# power_electronicsV5_1.net
KiCad netlist of a schematic drawn in EAGLE
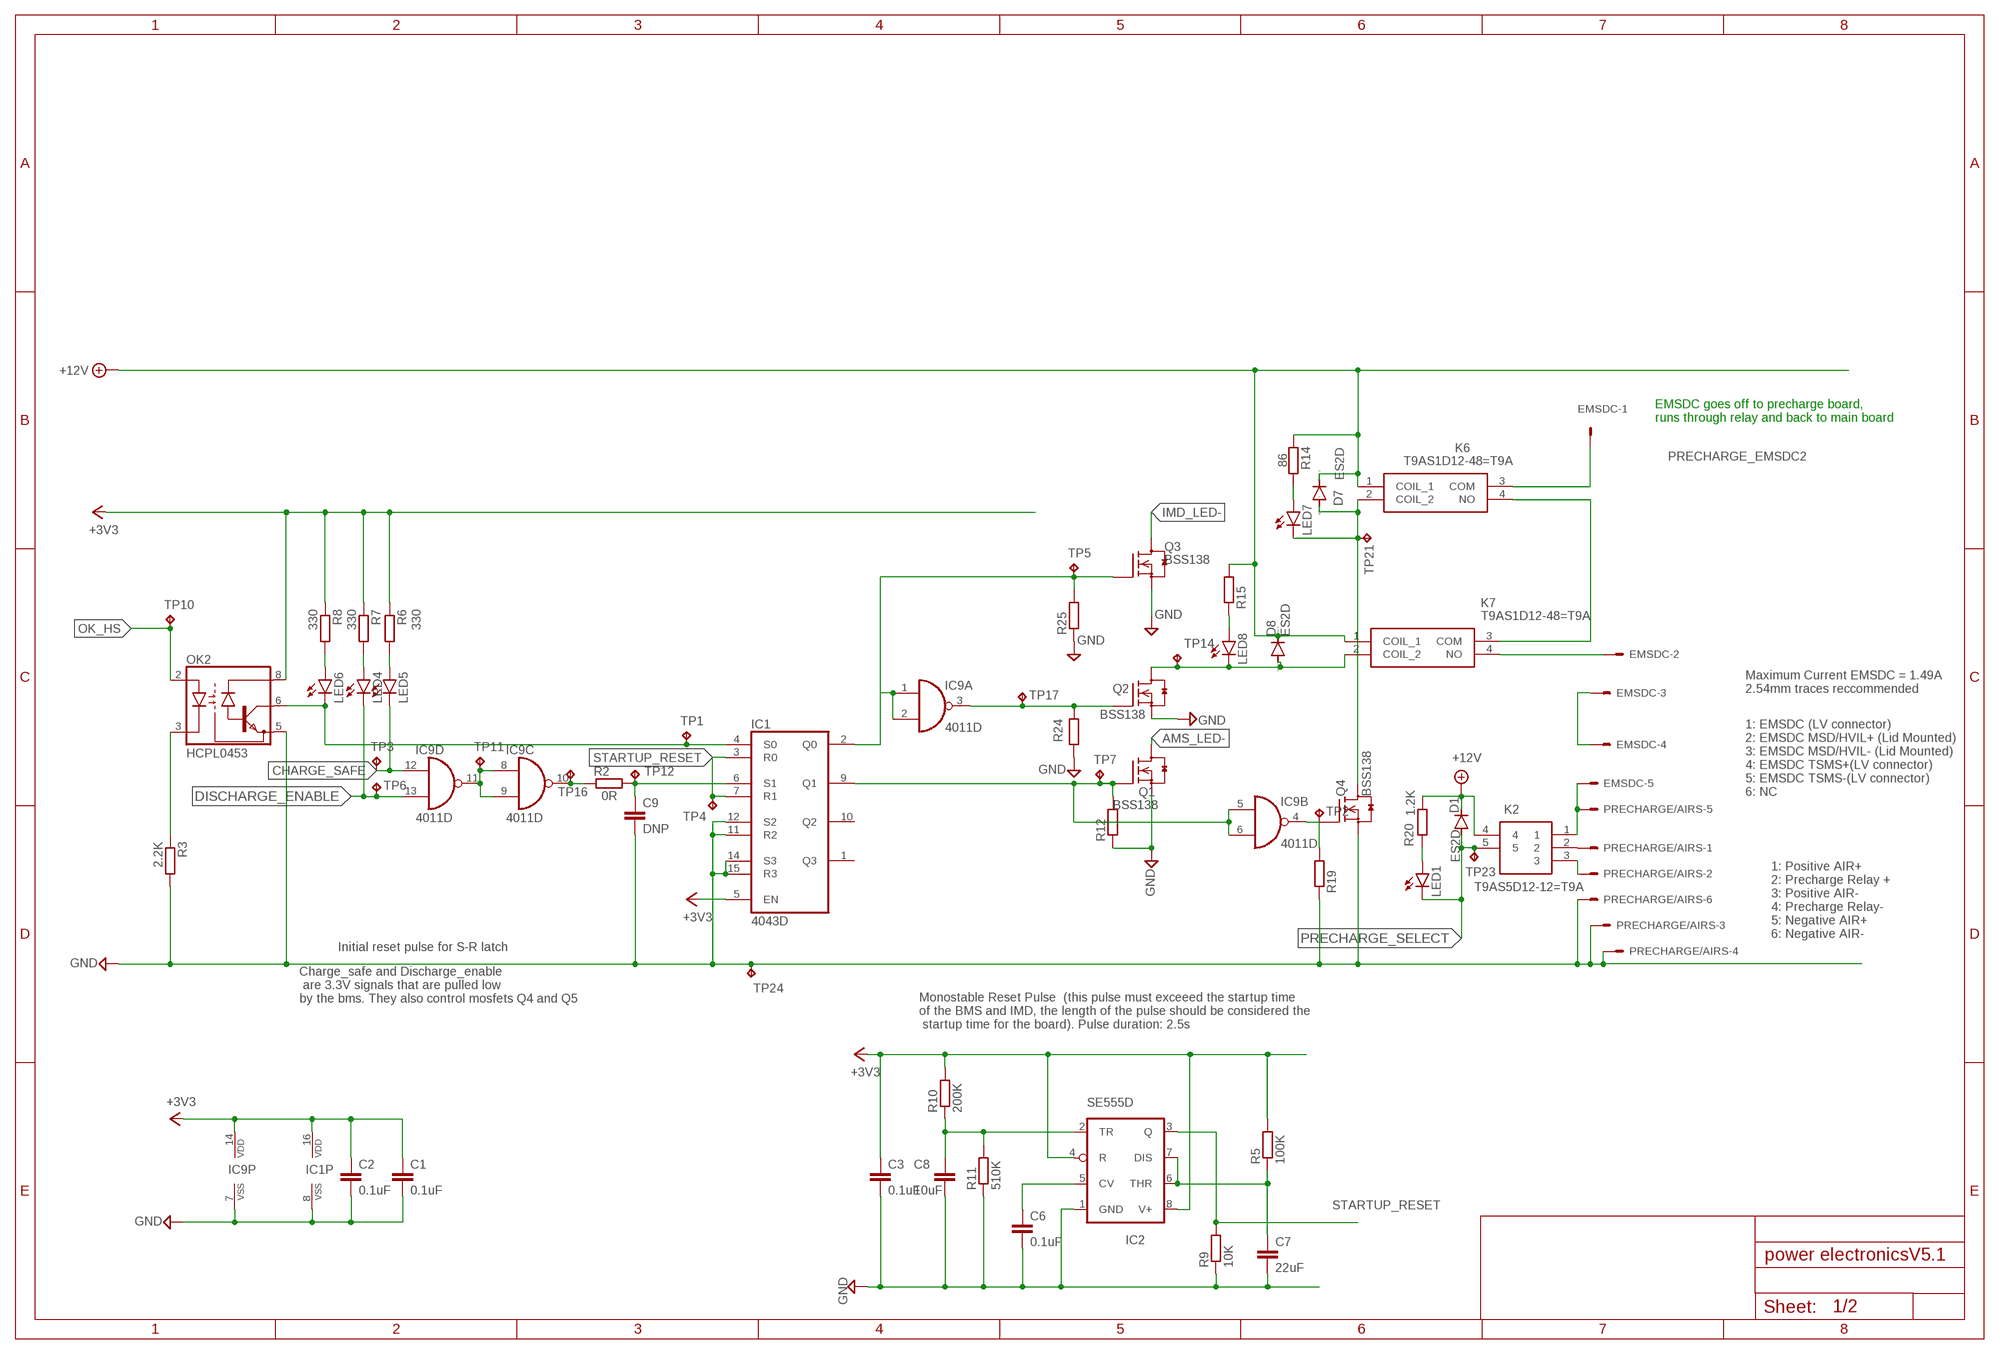
[diagram p0: schematic, sheet 1]
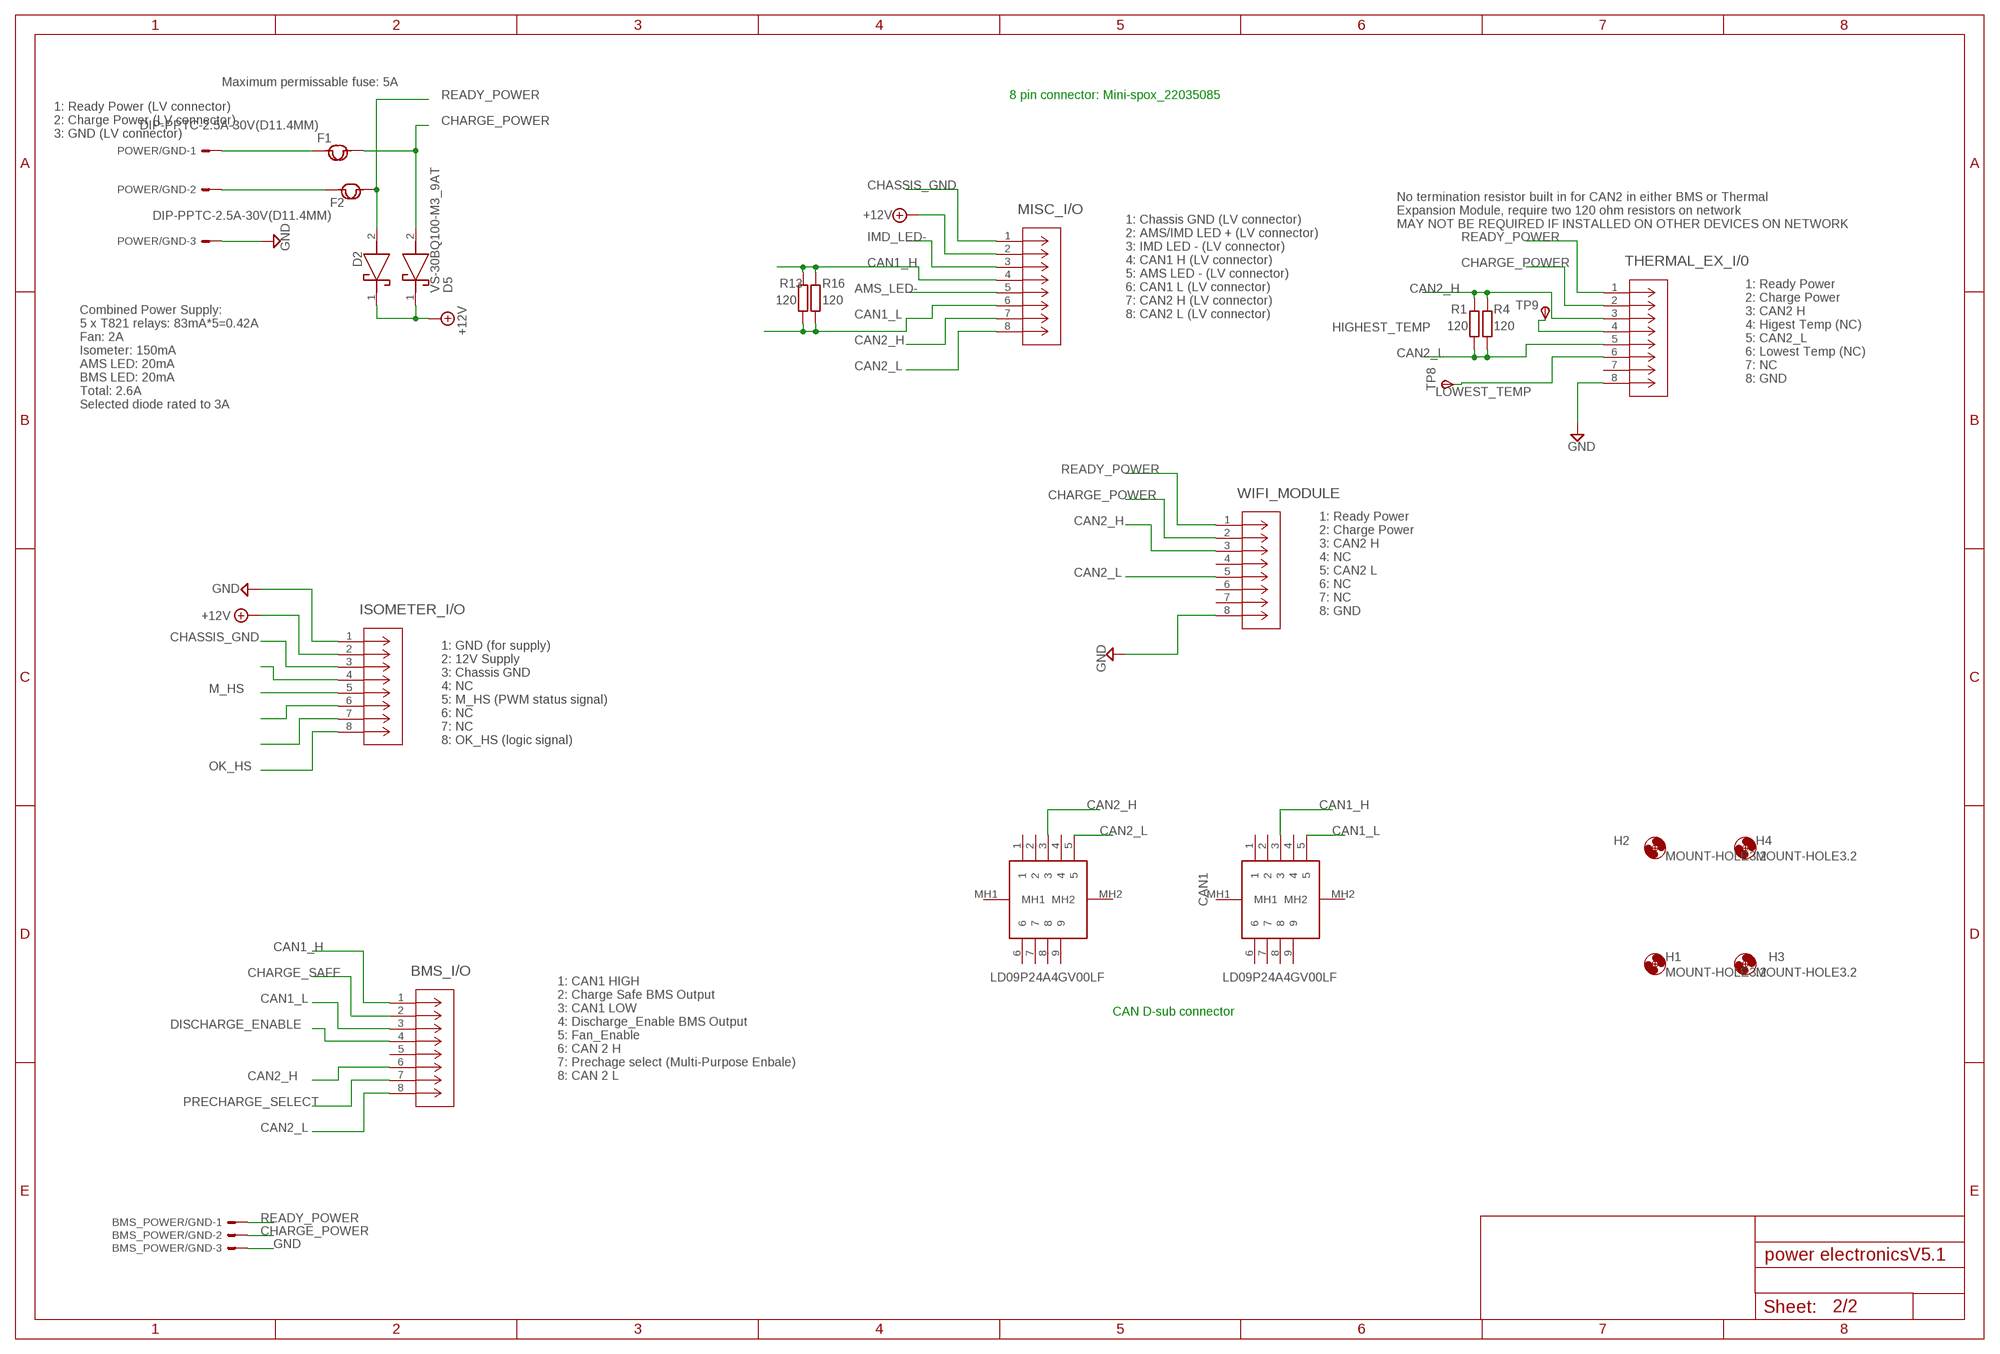
[diagram p1: schematic, sheet 2]

(export (version "E")
  (design (tool "Eeschema 10.0.6"))
  (components
    (comp (ref "C1")
      (value "0.1uF")
      (footprint "eagle-import:C0805")
      (fields (field (name "POPULARITY") "88F"))
      (libsource (lib "eagle-import") (part "C-EUC0805"))
    )
    (comp (ref "C2")
      (value "0.1uF")
      (footprint "eagle-import:C0805")
      (libsource (lib "eagle-import") (part "C-EUC0805"))
    )
    (comp (ref "C3")
      (value "0.1uF")
      (footprint "eagle-import:C0805")
      (libsource (lib "eagle-import") (part "C-EUC0805"))
    )
    (comp (ref "C6")
      (value "0.1uF")
      (footprint "eagle-import:C0805")
      (libsource (lib "eagle-import") (part "C-EUC0805"))
    )
    (comp (ref "C7")
      (value "22uF")
      (footprint "eagle-import:C1206")
      (libsource (lib "eagle-import") (part "C-EUC1206"))
    )
    (comp (ref "C8")
      (value "10uF")
      (footprint "eagle-import:C0805")
      (libsource (lib "eagle-import") (part "C-EUC0805"))
    )
    (comp (ref "C9")
      (value "DNP")
      (footprint "eagle-import:C0805K")
      (libsource (lib "eagle-import") (part "C-EUC0805K"))
    )
    (comp (ref "D1")
      (value "ES2D")
      (footprint "eagle-import:SMB")
      (libsource (lib "eagle-import") (part "ES2D"))
    )
    (comp (ref "D7")
      (value "ES2D")
      (footprint "eagle-import:SMB")
      (libsource (lib "eagle-import") (part "ES2D"))
    )
    (comp (ref "D8")
      (value "ES2D")
      (footprint "eagle-import:SMB")
      (libsource (lib "eagle-import") (part "ES2D"))
    )
    (comp (ref "EMSDC")
      (value "KK-156-6")
      (footprint "eagle-import:KK-156-6")
      (fields (field (name "MF") "MOLEX"))
      (libsource (lib "eagle-import") (part "KK-156-6"))
    )
    (comp (ref "IC1")
      (value "4043D")
      (footprint "eagle-import:SO16")
      (libsource (lib "eagle-import") (part "4043D"))
    )
    (comp (ref "IC2")
      (value "SE555D")
      (footprint "eagle-import:SO08")
      (libsource (lib "eagle-import") (part "555DSE"))
    )
    (comp (ref "IC9")
      (value "4011D")
      (footprint "eagle-import:SO14")
      (libsource (lib "eagle-import") (part "4011D"))
    )
    (comp (ref "K2")
      (value "T9AS5D12-12=T9A")
      (footprint "eagle-import:T9AS1D12")
      (fields (field (name "RS_PART_NUMBER") "6802528"))
      (libsource (lib "eagle-import") (part "T9AS5D12-12=T9A"))
    )
    (comp (ref "K6")
      (value "T9AS1D12-48=T9A")
      (footprint "eagle-import:T9AS1D1248T9A")
      (libsource (lib "eagle-import") (part "T9AS1D12-48=T9A"))
    )
    (comp (ref "K7")
      (value "T9AS1D12-48=T9A")
      (footprint "eagle-import:T9AS1D1248T9A")
      (libsource (lib "eagle-import") (part "T9AS1D12-48=T9A"))
    )
    (comp (ref "LED1")
      (value "LEDSML0805")
      (footprint "eagle-import:SML0805")
      (libsource (lib "eagle-import") (part "LEDSML0805"))
    )
    (comp (ref "LED4")
      (value "LEDSML0805")
      (footprint "eagle-import:SML0805")
      (libsource (lib "eagle-import") (part "LEDSML0805"))
    )
    (comp (ref "LED5")
      (value "LEDSML0805")
      (footprint "eagle-import:SML0805")
      (libsource (lib "eagle-import") (part "LEDSML0805"))
    )
    (comp (ref "LED6")
      (value "LEDSML0805")
      (footprint "eagle-import:SML0805")
      (libsource (lib "eagle-import") (part "LEDSML0805"))
    )
    (comp (ref "LED7")
      (value "LEDSML0805")
      (footprint "eagle-import:SML0805")
      (libsource (lib "eagle-import") (part "LEDSML0805"))
    )
    (comp (ref "LED8")
      (value "LEDSML0805")
      (footprint "eagle-import:SML0805")
      (libsource (lib "eagle-import") (part "LEDSML0805"))
    )
    (comp (ref "OK2")
      (value "HCPL0453")
      (footprint "eagle-import:SOIC08")
      (fields (field (name "MF") "AGILENT TECHNOLOGIES") (field (name "MPN") "HCPL-0453-000E"))
      (libsource (lib "eagle-import") (part "HCPL0453"))
    )
    (comp (ref "PRECHARGE/AIRS")
      (value "KK-156-6")
      (footprint "eagle-import:KK-156-6")
      (fields (field (name "MF") "MOLEX"))
      (libsource (lib "eagle-import") (part "KK-156-6"))
    )
    (comp (ref "Q1")
      (value "BSS138")
      (footprint "eagle-import:SOT23")
      (libsource (lib "eagle-import") (part "BSS138"))
    )
    (comp (ref "Q2")
      (value "BSS138")
      (footprint "eagle-import:SOT23")
      (libsource (lib "eagle-import") (part "BSS138"))
    )
    (comp (ref "Q3")
      (value "BSS138")
      (footprint "eagle-import:SOT23")
      (libsource (lib "eagle-import") (part "BSS138"))
    )
    (comp (ref "Q4")
      (value "BSS138")
      (footprint "eagle-import:SOT23")
      (libsource (lib "eagle-import") (part "BSS138"))
    )
    (comp (ref "R2")
      (value "0R")
      (footprint "eagle-import:R0805")
      (libsource (lib "eagle-import") (part "R-EU_R0805"))
    )
    (comp (ref "R3")
      (value "2.2K")
      (footprint "eagle-import:R0805")
      (libsource (lib "eagle-import") (part "R-EU_R0805"))
    )
    (comp (ref "R5")
      (value "100K")
      (footprint "eagle-import:R0805")
      (libsource (lib "eagle-import") (part "R-EU_R0805"))
    )
    (comp (ref "R6")
      (value "330")
      (footprint "eagle-import:R0805")
      (libsource (lib "eagle-import") (part "R-EU_R0805"))
    )
    (comp (ref "R7")
      (value "330")
      (footprint "eagle-import:R0805")
      (libsource (lib "eagle-import") (part "R-EU_R0805"))
    )
    (comp (ref "R8")
      (value "330")
      (footprint "eagle-import:R0805")
      (libsource (lib "eagle-import") (part "R-EU_R0805"))
    )
    (comp (ref "R9")
      (value "10K")
      (footprint "eagle-import:R0805")
      (libsource (lib "eagle-import") (part "R-EU_R0805"))
    )
    (comp (ref "R10")
      (value "200K")
      (footprint "eagle-import:R0805")
      (libsource (lib "eagle-import") (part "R-EU_R0805"))
    )
    (comp (ref "R11")
      (value "510K")
      (footprint "eagle-import:R0805")
      (libsource (lib "eagle-import") (part "R-EU_R0805"))
    )
    (comp (ref "R12")
      (value "R-EU_R0805")
      (footprint "eagle-import:R0805")
      (libsource (lib "eagle-import") (part "R-EU_R0805"))
    )
    (comp (ref "R14")
      (value "R-EU_R0805")
      (footprint "eagle-import:R0805")
      (fields (field (name "POPULARITY") "86"))
      (libsource (lib "eagle-import") (part "R-EU_R0805"))
    )
    (comp (ref "R15")
      (value "R-EU_R0805")
      (footprint "eagle-import:R0805")
      (libsource (lib "eagle-import") (part "R-EU_R0805"))
    )
    (comp (ref "R19")
      (value "R-EU_R0805")
      (footprint "eagle-import:R0805")
      (libsource (lib "eagle-import") (part "R-EU_R0805"))
    )
    (comp (ref "R20")
      (value "1.2K")
      (footprint "eagle-import:R0805")
      (libsource (lib "eagle-import") (part "R-EU_R0805"))
    )
    (comp (ref "R24")
      (value "R-EU_R0805")
      (footprint "eagle-import:R0805")
      (libsource (lib "eagle-import") (part "R-EU_R0805"))
    )
    (comp (ref "R25")
      (value "R-EU_R0805")
      (footprint "eagle-import:R0805")
      (libsource (lib "eagle-import") (part "R-EU_R0805"))
    )
    (comp (ref "TP1")
      (value "TPPAD1-17")
      (footprint "eagle-import:P1-17")
      (libsource (lib "eagle-import") (part "TPPAD1-17"))
    )
    (comp (ref "TP2")
      (value "TPPAD1-17")
      (footprint "eagle-import:P1-17")
      (libsource (lib "eagle-import") (part "TPPAD1-17"))
    )
    (comp (ref "TP3")
      (value "TPPAD1-17")
      (footprint "eagle-import:P1-17")
      (libsource (lib "eagle-import") (part "TPPAD1-17"))
    )
    (comp (ref "TP4")
      (value "TPPAD1-17")
      (footprint "eagle-import:P1-17")
      (libsource (lib "eagle-import") (part "TPPAD1-17"))
    )
    (comp (ref "TP5")
      (value "TPPAD1-17")
      (footprint "eagle-import:P1-17")
      (libsource (lib "eagle-import") (part "TPPAD1-17"))
    )
    (comp (ref "TP6")
      (value "TPPAD1-17")
      (footprint "eagle-import:P1-17")
      (libsource (lib "eagle-import") (part "TPPAD1-17"))
    )
    (comp (ref "TP7")
      (value "TPPAD1-17")
      (footprint "eagle-import:P1-17")
      (libsource (lib "eagle-import") (part "TPPAD1-17"))
    )
    (comp (ref "TP10")
      (value "TPPAD1-17")
      (footprint "eagle-import:P1-17")
      (libsource (lib "eagle-import") (part "TPPAD1-17"))
    )
    (comp (ref "TP11")
      (value "TPPAD1-17")
      (footprint "eagle-import:P1-17")
      (libsource (lib "eagle-import") (part "TPPAD1-17"))
    )
    (comp (ref "TP12")
      (value "TPPAD1-17")
      (footprint "eagle-import:P1-17")
      (libsource (lib "eagle-import") (part "TPPAD1-17"))
    )
    (comp (ref "TP14")
      (value "TPPAD1-17")
      (footprint "eagle-import:P1-17")
      (libsource (lib "eagle-import") (part "TPPAD1-17"))
    )
    (comp (ref "TP16")
      (value "TPPAD1-17")
      (footprint "eagle-import:P1-17")
      (libsource (lib "eagle-import") (part "TPPAD1-17"))
    )
    (comp (ref "TP17")
      (value "TPPAD1-17")
      (footprint "eagle-import:P1-17")
      (libsource (lib "eagle-import") (part "TPPAD1-17"))
    )
    (comp (ref "TP21")
      (value "TPPAD1-17")
      (footprint "eagle-import:P1-17")
      (libsource (lib "eagle-import") (part "TPPAD1-17"))
    )
    (comp (ref "TP23")
      (value "TPPAD1-17")
      (footprint "eagle-import:P1-17")
      (libsource (lib "eagle-import") (part "TPPAD1-17"))
    )
    (comp (ref "TP24")
      (value "TPPAD1-17")
      (footprint "eagle-import:P1-17")
      (libsource (lib "eagle-import") (part "TPPAD1-17"))
    )
    (comp (ref "BMS_I/O")
      (value "MINI-SPOX_22035085")
      (footprint "eagle-import:CON_22035085_MOL")
      (fields
        (field (name "MANUFACTURER_PART_NUMBER") "22035085")
        (field (name "COPYRIGHT") "Copyright (C) 2023 Ultra Librarian. All rights reserved.")
      )
      (libsource (lib "eagle-import") (part "MINI-SPOX_22035085"))
    )
    (comp (ref "BMS_POWER/GND")
      (value "KK-156-3")
      (footprint "eagle-import:KK-156-3")
      (fields (field (name "MF") "MOLEX"))
      (libsource (lib "eagle-import") (part "KK-156-3"))
    )
    (comp (ref "CAN1")
      (value "LD09P24A4GV00LF")
      (footprint "eagle-import:LD09P24A4GV00LF")
      (fields (field (name "MOUSER_PART_NUMBER") "649-LD09P24A4GV00LF"))
      (libsource (lib "eagle-import") (part "LD09P24A4GV00LF"))
    )
    (comp (ref "CAN2")
      (value "LD09P24A4GV00LF")
      (footprint "eagle-import:LD09P24A4GV00LF")
      (fields (field (name "MOUSER_PART_NUMBER") "649-LD09P24A4GV00LF"))
      (libsource (lib "eagle-import") (part "LD09P24A4GV00LF"))
    )
    (comp (ref "D2")
      (value "VS-30BQ100-M3_9AT")
      (footprint "eagle-import:DIOM7959X262N")
      (fields
        (field (name "MANUFACTURER_PART_NUMBER") "VS-30BQ100-M3/9AT")
        (field (name "MOUSER_PART_NUMBER") "78-VS-30BQ100-M39AT")
      )
      (libsource (lib "eagle-import") (part "VS-30BQ100-M3_9AT"))
    )
    (comp (ref "D5")
      (value "VS-30BQ100-M3_9AT")
      (footprint "eagle-import:DIOM7959X262N")
      (fields
        (field (name "MANUFACTURER_PART_NUMBER") "VS-30BQ100-M3/9AT")
        (field (name "MOUSER_PART_NUMBER") "78-VS-30BQ100-M39AT")
      )
      (libsource (lib "eagle-import") (part "VS-30BQ100-M3_9AT"))
    )
    (comp (ref "F1")
      (value "DIP-PPTC-2.5A-30V(D11.4MM)")
      (footprint "eagle-import:F2-5.1-11.4X3.0X18.3MM")
      (fields (field (name "MF") "Littelfuse") (field (name "MP") "30R250"))
      (libsource (lib "eagle-import") (part "DIP-PPTC-2.5A-30V(D11.4MM)"))
    )
    (comp (ref "F2")
      (value "DIP-PPTC-2.5A-30V(D11.4MM)")
      (footprint "eagle-import:F2-5.1-11.4X3.0X18.3MM")
      (fields (field (name "MF") "Littelfuse") (field (name "MP") "30R250"))
      (libsource (lib "eagle-import") (part "DIP-PPTC-2.5A-30V(D11.4MM)"))
    )
    (comp (ref "H1")
      (value "MOUNT-HOLE3.2")
      (footprint "eagle-import:3,2")
      (libsource (lib "eagle-import") (part "MOUNT-HOLE3.2"))
    )
    (comp (ref "H2")
      (value "MOUNT-HOLE3.2")
      (footprint "eagle-import:3,2")
      (libsource (lib "eagle-import") (part "MOUNT-HOLE3.2"))
    )
    (comp (ref "H3")
      (value "MOUNT-HOLE3.2")
      (footprint "eagle-import:3,2")
      (libsource (lib "eagle-import") (part "MOUNT-HOLE3.2"))
    )
    (comp (ref "H4")
      (value "MOUNT-HOLE3.2")
      (footprint "eagle-import:3,2")
      (libsource (lib "eagle-import") (part "MOUNT-HOLE3.2"))
    )
    (comp (ref "ISOMETER_I/O")
      (value "MINI-SPOX_22035085")
      (footprint "eagle-import:CON_22035085_MOL")
      (fields
        (field (name "MANUFACTURER_PART_NUMBER") "22035085")
        (field (name "COPYRIGHT") "Copyright (C) 2023 Ultra Librarian. All rights reserved.")
      )
      (libsource (lib "eagle-import") (part "MINI-SPOX_22035085"))
    )
    (comp (ref "MISC_I/O")
      (value "MINI-SPOX_22035085")
      (footprint "eagle-import:CON_22035085_MOL")
      (fields
        (field (name "MANUFACTURER_PART_NUMBER") "22035085")
        (field (name "COPYRIGHT") "Copyright (C) 2023 Ultra Librarian. All rights reserved.")
      )
      (libsource (lib "eagle-import") (part "MINI-SPOX_22035085"))
    )
    (comp (ref "POWER/GND")
      (value "KK-156-3")
      (footprint "eagle-import:KK-156-3")
      (fields (field (name "MF") "MOLEX"))
      (libsource (lib "eagle-import") (part "KK-156-3"))
    )
    (comp (ref "R1")
      (value "120")
      (footprint "eagle-import:R1206")
      (libsource (lib "eagle-import") (part "R-EU_R1206"))
    )
    (comp (ref "R4")
      (value "120")
      (footprint "eagle-import:R1206")
      (libsource (lib "eagle-import") (part "R-EU_R1206"))
    )
    (comp (ref "R13")
      (value "120")
      (footprint "eagle-import:R1206")
      (libsource (lib "eagle-import") (part "R-EU_R1206"))
    )
    (comp (ref "R16")
      (value "120")
      (footprint "eagle-import:R1206")
      (libsource (lib "eagle-import") (part "R-EU_R1206"))
    )
    (comp (ref "THERMAL_EX_I/0")
      (value "MINI-SPOX_22035085")
      (footprint "eagle-import:CON_22035085_MOL")
      (fields
        (field (name "MANUFACTURER_PART_NUMBER") "22035085")
        (field (name "COPYRIGHT") "Copyright (C) 2023 Ultra Librarian. All rights reserved.")
      )
      (libsource (lib "eagle-import") (part "MINI-SPOX_22035085"))
    )
    (comp (ref "TP8")
      (value "TPSTP11R")
      (footprint "eagle-import:TP11R")
      (libsource (lib "eagle-import") (part "TPSTP11R"))
    )
    (comp (ref "TP9")
      (value "TPSTP11R")
      (footprint "eagle-import:TP11R")
      (libsource (lib "eagle-import") (part "TPSTP11R"))
    )
    (comp (ref "WIFI_MODULE")
      (value "MINI-SPOX_22035085")
      (footprint "eagle-import:CON_22035085_MOL")
      (fields
        (field (name "MANUFACTURER_PART_NUMBER") "22035085")
        (field (name "COPYRIGHT") "Copyright (C) 2023 Ultra Librarian. All rights reserved.")
      )
      (libsource (lib "eagle-import") (part "MINI-SPOX_22035085"))
    )
  )
  (nets
    (net (code "1") (name "+3V3") (class "Default")
      (node (ref "C1") (pin "1") (pinfunction "1_1") (pintype "passive"))
      (node (ref "C2") (pin "1") (pinfunction "1_1") (pintype "passive"))
      (node (ref "C3") (pin "1") (pinfunction "1_1") (pintype "passive"))
      (node (ref "IC1") (pin "16") (pinfunction "VDD_16") (pintype "power_in"))
      (node (ref "IC1") (pin "5") (pinfunction "EN_5") (pintype "input"))
      (node (ref "IC2") (pin "4") (pinfunction "R_4") (pintype "input"))
      (node (ref "IC2") (pin "8") (pinfunction "V+_8") (pintype "power_in"))
      (node (ref "IC9") (pin "14") (pinfunction "VDD_14") (pintype "power_in"))
      (node (ref "OK2") (pin "8") (pinfunction "VCC_8") (pintype "passive"))
      (node (ref "R10") (pin "2") (pinfunction "2_2") (pintype "passive"))
      (node (ref "R5") (pin "2") (pinfunction "2_2") (pintype "passive"))
      (node (ref "R6") (pin "1") (pinfunction "1_1") (pintype "passive"))
      (node (ref "R7") (pin "1") (pinfunction "1_1") (pintype "passive"))
      (node (ref "R8") (pin "1") (pinfunction "1_1") (pintype "passive"))
    )
    (net (code "2") (name "+12V") (class "Default")
      (node (ref "D1") (pin "C") (pinfunction "C_C") (pintype "passive"))
      (node (ref "D2") (pin "1") (pinfunction "K_1") (pintype "bidirectional"))
      (node (ref "D5") (pin "1") (pinfunction "K_1") (pintype "bidirectional"))
      (node (ref "D7") (pin "C") (pinfunction "C_C") (pintype "passive"))
      (node (ref "D8") (pin "C") (pinfunction "C_C") (pintype "passive"))
      (node (ref "ISOMETER_I/O") (pin "2") (pinfunction "2_2") (pintype "passive"))
      (node (ref "K2") (pin "4") (pinfunction "4_4") (pintype "bidirectional"))
      (node (ref "K6") (pin "1") (pinfunction "COIL_1_1") (pintype "bidirectional"))
      (node (ref "K7") (pin "1") (pinfunction "COIL_1_1") (pintype "bidirectional"))
      (node (ref "MISC_I/O") (pin "2") (pinfunction "2_2") (pintype "passive"))
      (node (ref "R14") (pin "2") (pinfunction "2_2") (pintype "passive"))
      (node (ref "R15") (pin "2") (pinfunction "2_2") (pintype "passive"))
      (node (ref "R20") (pin "1") (pinfunction "1_1") (pintype "passive"))
    )
    (net (code "3") (name "AMS_LED-") (class "Default")
      (node (ref "MISC_I/O") (pin "5") (pinfunction "5_5") (pintype "passive"))
      (node (ref "Q1") (pin "3") (pinfunction "D_3") (pintype "passive"))
    )
    (net (code "4") (name "CAN1_H") (class "Default")
      (node (ref "BMS_I/O") (pin "1") (pinfunction "1_1") (pintype "passive"))
      (node (ref "CAN1") (pin "3") (pinfunction "3_3") (pintype "bidirectional"))
      (node (ref "MISC_I/O") (pin "4") (pinfunction "4_4") (pintype "passive"))
      (node (ref "R13") (pin "1") (pinfunction "1_1") (pintype "passive"))
      (node (ref "R16") (pin "1") (pinfunction "1_1") (pintype "passive"))
    )
    (net (code "5") (name "CAN1_L") (class "Default")
      (node (ref "BMS_I/O") (pin "3") (pinfunction "3_3") (pintype "passive"))
      (node (ref "CAN1") (pin "5") (pinfunction "5_5") (pintype "bidirectional"))
      (node (ref "MISC_I/O") (pin "6") (pinfunction "6_6") (pintype "passive"))
      (node (ref "R13") (pin "2") (pinfunction "2_2") (pintype "passive"))
      (node (ref "R16") (pin "2") (pinfunction "2_2") (pintype "passive"))
    )
    (net (code "6") (name "CAN2_H") (class "Default")
      (node (ref "BMS_I/O") (pin "6") (pinfunction "6_6") (pintype "passive"))
      (node (ref "CAN2") (pin "3") (pinfunction "3_3") (pintype "bidirectional"))
      (node (ref "MISC_I/O") (pin "7") (pinfunction "7_7") (pintype "passive"))
      (node (ref "R1") (pin "1") (pinfunction "1_1") (pintype "passive"))
      (node (ref "R4") (pin "1") (pinfunction "1_1") (pintype "passive"))
      (node (ref "THERMAL_EX_I/0") (pin "3") (pinfunction "3_3") (pintype "passive"))
      (node (ref "WIFI_MODULE") (pin "3") (pinfunction "3_3") (pintype "passive"))
    )
    (net (code "7") (name "CAN2_L") (class "Default")
      (node (ref "BMS_I/O") (pin "8") (pinfunction "8_8") (pintype "passive"))
      (node (ref "CAN2") (pin "5") (pinfunction "5_5") (pintype "bidirectional"))
      (node (ref "MISC_I/O") (pin "8") (pinfunction "8_8") (pintype "passive"))
      (node (ref "R1") (pin "2") (pinfunction "2_2") (pintype "passive"))
      (node (ref "R4") (pin "2") (pinfunction "2_2") (pintype "passive"))
      (node (ref "THERMAL_EX_I/0") (pin "5") (pinfunction "5_5") (pintype "passive"))
      (node (ref "WIFI_MODULE") (pin "5") (pinfunction "5_5") (pintype "passive"))
    )
    (net (code "8") (name "CHARGE_POWER") (class "Default")
      (node (ref "BMS_POWER/GND") (pin "2") (pinfunction "S_2") (pintype "passive"))
      (node (ref "D5") (pin "2") (pinfunction "A_2") (pintype "bidirectional"))
      (node (ref "F1") (pin "1") (pinfunction "1_1") (pintype "bidirectional"))
      (node (ref "THERMAL_EX_I/0") (pin "2") (pinfunction "2_2") (pintype "passive"))
      (node (ref "WIFI_MODULE") (pin "2") (pinfunction "2_2") (pintype "passive"))
    )
    (net (code "9") (name "CHARGE_SAFE") (class "Default")
      (node (ref "BMS_I/O") (pin "2") (pinfunction "2_2") (pintype "passive"))
      (node (ref "IC9") (pin "12") (pinfunction "I0_12") (pintype "input"))
      (node (ref "LED5") (pin "C") (pinfunction "C_C") (pintype "passive"))
      (node (ref "TP3") (pin "TP") (pinfunction "TP_TP") (pintype "input"))
    )
    (net (code "10") (name "CHASSIS_GND") (class "Default")
      (node (ref "ISOMETER_I/O") (pin "3") (pinfunction "3_3") (pintype "passive"))
      (node (ref "MISC_I/O") (pin "1") (pinfunction "1_1") (pintype "passive"))
    )
    (net (code "11") (name "DISCHARGE_ENABLE") (class "Default")
      (node (ref "BMS_I/O") (pin "4") (pinfunction "4_4") (pintype "passive"))
      (node (ref "IC1") (pin "9") (pinfunction "Q1_9") (pintype "output"))
      (node (ref "IC9") (pin "13") (pinfunction "I1_13") (pintype "input"))
      (node (ref "IC9") (pin "5") (pinfunction "I0_5") (pintype "input"))
      (node (ref "IC9") (pin "6") (pinfunction "I1_6") (pintype "input"))
      (node (ref "LED4") (pin "C") (pinfunction "C_C") (pintype "passive"))
      (node (ref "Q1") (pin "1") (pinfunction "G_1") (pintype "passive"))
      (node (ref "R12") (pin "2") (pinfunction "2_2") (pintype "passive"))
      (node (ref "TP6") (pin "TP") (pinfunction "TP_TP") (pintype "input"))
      (node (ref "TP7") (pin "TP") (pinfunction "TP_TP") (pintype "input"))
    )
    (net (code "12") (name "GND") (class "Default")
      (node (ref "BMS_POWER/GND") (pin "3") (pinfunction "S_3") (pintype "passive"))
      (node (ref "C1") (pin "2") (pinfunction "2_2") (pintype "passive"))
      (node (ref "C2") (pin "2") (pinfunction "2_2") (pintype "passive"))
      (node (ref "C3") (pin "2") (pinfunction "2_2") (pintype "passive"))
      (node (ref "C6") (pin "2") (pinfunction "2_2") (pintype "passive"))
      (node (ref "C7") (pin "2") (pinfunction "2_2") (pintype "passive"))
      (node (ref "C8") (pin "2") (pinfunction "2_2") (pintype "passive"))
      (node (ref "C9") (pin "2") (pinfunction "2_2") (pintype "passive"))
      (node (ref "IC1") (pin "11") (pinfunction "R2_11") (pintype "input"))
      (node (ref "IC1") (pin "12") (pinfunction "S2_12") (pintype "input"))
      (node (ref "IC1") (pin "14") (pinfunction "S3_14") (pintype "input"))
      (node (ref "IC1") (pin "15") (pinfunction "R3_15") (pintype "input"))
      (node (ref "IC1") (pin "8") (pinfunction "VSS_8") (pintype "power_in"))
      (node (ref "IC2") (pin "1") (pinfunction "GND_1") (pintype "power_in"))
      (node (ref "IC9") (pin "7") (pinfunction "VSS_7") (pintype "power_in"))
      (node (ref "ISOMETER_I/O") (pin "1") (pinfunction "1_1") (pintype "passive"))
      (node (ref "OK2") (pin "5") (pinfunction "GND_5") (pintype "passive"))
      (node (ref "POWER/GND") (pin "3") (pinfunction "S_3") (pintype "passive"))
      (node (ref "PRECHARGE/AIRS") (pin "3") (pinfunction "S_3") (pintype "passive"))
      (node (ref "PRECHARGE/AIRS") (pin "4") (pinfunction "S_4") (pintype "passive"))
      (node (ref "PRECHARGE/AIRS") (pin "6") (pinfunction "S_6") (pintype "passive"))
      (node (ref "Q1") (pin "2") (pinfunction "S_2") (pintype "passive"))
      (node (ref "Q2") (pin "2") (pinfunction "S_2") (pintype "passive"))
      (node (ref "Q3") (pin "2") (pinfunction "S_2") (pintype "passive"))
      (node (ref "Q4") (pin "2") (pinfunction "S_2") (pintype "passive"))
      (node (ref "R11") (pin "1") (pinfunction "1_1") (pintype "passive"))
      (node (ref "R12") (pin "1") (pinfunction "1_1") (pintype "passive"))
      (node (ref "R19") (pin "1") (pinfunction "1_1") (pintype "passive"))
      (node (ref "R24") (pin "1") (pinfunction "1_1") (pintype "passive"))
      (node (ref "R25") (pin "1") (pinfunction "1_1") (pintype "passive"))
      (node (ref "R3") (pin "2") (pinfunction "2_2") (pintype "passive"))
      (node (ref "R9") (pin "1") (pinfunction "1_1") (pintype "passive"))
      (node (ref "THERMAL_EX_I/0") (pin "8") (pinfunction "8_8") (pintype "passive"))
      (node (ref "TP24") (pin "TP") (pinfunction "TP_TP") (pintype "input"))
      (node (ref "WIFI_MODULE") (pin "8") (pinfunction "8_8") (pintype "passive"))
    )
    (net (code "13") (name "HIGHEST_TEMP") (class "Default")
      (node (ref "THERMAL_EX_I/0") (pin "4") (pinfunction "4_4") (pintype "passive"))
      (node (ref "TP9") (pin "TP") (pinfunction "PP_TP") (pintype "input"))
    )
    (net (code "14") (name "IMD_LED-") (class "Default")
      (node (ref "MISC_I/O") (pin "3") (pinfunction "3_3") (pintype "passive"))
      (node (ref "Q3") (pin "3") (pinfunction "D_3") (pintype "passive"))
    )
    (net (code "15") (name "LOWEST_TEMP") (class "Default")
      (node (ref "THERMAL_EX_I/0") (pin "6") (pinfunction "6_6") (pintype "passive"))
      (node (ref "TP8") (pin "TP") (pinfunction "PP_TP") (pintype "input"))
    )
    (net (code "16") (name "M_HS") (class "Default")
      (node (ref "ISOMETER_I/O") (pin "5") (pinfunction "5_5") (pintype "passive"))
    )
    (net (code "17") (name "Net-(EMSDCB-S)") (class "Default")
      (node (ref "EMSDC") (pin "2") (pinfunction "S_2") (pintype "passive"))
      (node (ref "K7") (pin "4") (pinfunction "NO_4") (pintype "bidirectional"))
    )
    (net (code "18") (name "Net-(EMSDCC-S)") (class "Default")
      (node (ref "EMSDC") (pin "3") (pinfunction "S_3") (pintype "passive"))
      (node (ref "EMSDC") (pin "4") (pinfunction "S_4") (pintype "passive"))
    )
    (net (code "19") (name "Net-(EMSDCE-S)") (class "Default")
      (node (ref "EMSDC") (pin "5") (pinfunction "S_5") (pintype "passive"))
      (node (ref "K2") (pin "1") (pinfunction "1_1") (pintype "bidirectional"))
      (node (ref "PRECHARGE/AIRS") (pin "5") (pinfunction "S_5") (pintype "passive"))
    )
    (net (code "20") (name "Net-(IC1A-Q0)") (class "Default")
      (node (ref "IC1") (pin "2") (pinfunction "Q0_2") (pintype "output"))
      (node (ref "IC9") (pin "1") (pinfunction "I0_1") (pintype "input"))
      (node (ref "IC9") (pin "2") (pinfunction "I1_2") (pintype "input"))
      (node (ref "Q3") (pin "1") (pinfunction "G_1") (pintype "passive"))
      (node (ref "R25") (pin "2") (pinfunction "2_2") (pintype "passive"))
      (node (ref "TP5") (pin "TP") (pinfunction "TP_TP") (pintype "input"))
    )
    (net (code "21") (name "Net-(IC1A-S0)") (class "Default")
      (node (ref "IC1") (pin "4") (pinfunction "S0_4") (pintype "input"))
      (node (ref "LED6") (pin "C") (pinfunction "C_C") (pintype "passive"))
      (node (ref "OK2") (pin "6") (pinfunction "VO_6") (pintype "passive"))
      (node (ref "TP1") (pin "TP") (pinfunction "TP_TP") (pintype "input"))
    )
    (net (code "22") (name "Net-(IC1A-S1)") (class "Default")
      (node (ref "C9") (pin "1") (pinfunction "1_1") (pintype "passive"))
      (node (ref "IC1") (pin "6") (pinfunction "S1_6") (pintype "input"))
      (node (ref "R2") (pin "2") (pinfunction "2_2") (pintype "passive"))
      (node (ref "TP12") (pin "TP") (pinfunction "TP_TP") (pintype "input"))
    )
    (net (code "23") (name "Net-(IC2-CV)") (class "Default")
      (node (ref "C6") (pin "1") (pinfunction "1_1") (pintype "passive"))
      (node (ref "IC2") (pin "5") (pinfunction "CV_5") (pintype "input"))
    )
    (net (code "24") (name "Net-(IC2-DIS)") (class "Default")
      (node (ref "C7") (pin "1") (pinfunction "1_1") (pintype "passive"))
      (node (ref "IC2") (pin "6") (pinfunction "THR_6") (pintype "input"))
      (node (ref "IC2") (pin "7") (pinfunction "DIS_7") (pintype "input"))
      (node (ref "R5") (pin "1") (pinfunction "1_1") (pintype "passive"))
    )
    (net (code "25") (name "Net-(IC2-TR)") (class "Default")
      (node (ref "C8") (pin "1") (pinfunction "1_1") (pintype "passive"))
      (node (ref "IC2") (pin "2") (pinfunction "TR_2") (pintype "input"))
      (node (ref "R10") (pin "1") (pinfunction "1_1") (pintype "passive"))
      (node (ref "R11") (pin "2") (pinfunction "2_2") (pintype "passive"))
    )
    (net (code "26") (name "Net-(IC9A-O)") (class "Default")
      (node (ref "IC9") (pin "3") (pinfunction "O_3") (pintype "output"))
      (node (ref "Q2") (pin "1") (pinfunction "G_1") (pintype "passive"))
      (node (ref "R24") (pin "2") (pinfunction "2_2") (pintype "passive"))
      (node (ref "TP17") (pin "TP") (pinfunction "TP_TP") (pintype "input"))
    )
    (net (code "27") (name "Net-(IC9B-O)") (class "Default")
      (node (ref "IC9") (pin "4") (pinfunction "O_4") (pintype "output"))
      (node (ref "Q4") (pin "1") (pinfunction "G_1") (pintype "passive"))
      (node (ref "R19") (pin "2") (pinfunction "2_2") (pintype "passive"))
      (node (ref "TP2") (pin "TP") (pinfunction "TP_TP") (pintype "input"))
    )
    (net (code "28") (name "Net-(IC9C-I0)") (class "Default")
      (node (ref "IC9") (pin "11") (pinfunction "O_11") (pintype "output"))
      (node (ref "IC9") (pin "8") (pinfunction "I0_8") (pintype "input"))
      (node (ref "IC9") (pin "9") (pinfunction "I1_9") (pintype "input"))
      (node (ref "TP11") (pin "TP") (pinfunction "TP_TP") (pintype "input"))
    )
    (net (code "29") (name "Net-(IC9C-O)") (class "Default")
      (node (ref "IC9") (pin "10") (pinfunction "O_10") (pintype "output"))
      (node (ref "R2") (pin "1") (pinfunction "1_1") (pintype "passive"))
      (node (ref "TP16") (pin "TP") (pinfunction "TP_TP") (pintype "input"))
    )
    (net (code "30") (name "Net-(K6-COIL_2)") (class "Default")
      (node (ref "D7") (pin "A") (pinfunction "A_A") (pintype "passive"))
      (node (ref "K6") (pin "2") (pinfunction "COIL_2_2") (pintype "bidirectional"))
      (node (ref "LED7") (pin "C") (pinfunction "C_C") (pintype "passive"))
      (node (ref "Q4") (pin "3") (pinfunction "D_3") (pintype "passive"))
      (node (ref "TP21") (pin "TP") (pinfunction "TP_TP") (pintype "input"))
    )
    (net (code "31") (name "Net-(K6-NO)") (class "Default")
      (node (ref "K6") (pin "4") (pinfunction "NO_4") (pintype "bidirectional"))
      (node (ref "K7") (pin "3") (pinfunction "COM_3") (pintype "bidirectional"))
    )
    (net (code "32") (name "Net-(K7-COIL_2)") (class "Default")
      (node (ref "D8") (pin "A") (pinfunction "A_A") (pintype "passive"))
      (node (ref "K7") (pin "2") (pinfunction "COIL_2_2") (pintype "bidirectional"))
      (node (ref "LED8") (pin "C") (pinfunction "C_C") (pintype "passive"))
      (node (ref "Q2") (pin "3") (pinfunction "D_3") (pintype "passive"))
      (node (ref "TP14") (pin "TP") (pinfunction "TP_TP") (pintype "input"))
    )
    (net (code "33") (name "Net-(LED1-PadA)") (class "Default")
      (node (ref "LED1") (pin "A") (pinfunction "A_A") (pintype "passive"))
      (node (ref "R20") (pin "2") (pinfunction "2_2") (pintype "passive"))
    )
    (net (code "34") (name "Net-(LED4-PadA)") (class "Default")
      (node (ref "LED4") (pin "A") (pinfunction "A_A") (pintype "passive"))
      (node (ref "R7") (pin "2") (pinfunction "2_2") (pintype "passive"))
    )
    (net (code "35") (name "Net-(LED5-PadA)") (class "Default")
      (node (ref "LED5") (pin "A") (pinfunction "A_A") (pintype "passive"))
      (node (ref "R6") (pin "2") (pinfunction "2_2") (pintype "passive"))
    )
    (net (code "36") (name "Net-(LED6-PadA)") (class "Default")
      (node (ref "LED6") (pin "A") (pinfunction "A_A") (pintype "passive"))
      (node (ref "R8") (pin "2") (pinfunction "2_2") (pintype "passive"))
    )
    (net (code "37") (name "Net-(LED7-PadA)") (class "Default")
      (node (ref "LED7") (pin "A") (pinfunction "A_A") (pintype "passive"))
      (node (ref "R14") (pin "1") (pinfunction "1_1") (pintype "passive"))
    )
    (net (code "38") (name "Net-(LED8-PadA)") (class "Default")
      (node (ref "LED8") (pin "A") (pinfunction "A_A") (pintype "passive"))
      (node (ref "R15") (pin "1") (pinfunction "1_1") (pintype "passive"))
    )
    (net (code "39") (name "Net-(OK2-C)") (class "Default")
      (node (ref "OK2") (pin "3") (pinfunction "C_3") (pintype "passive"))
      (node (ref "R3") (pin "1") (pinfunction "1_1") (pintype "passive"))
    )
    (net (code "40") (name "Net-(POWER/GNDA-S)") (class "Default")
      (node (ref "F1") (pin "2") (pinfunction "2_2") (pintype "bidirectional"))
      (node (ref "POWER/GND") (pin "1") (pinfunction "S_1") (pintype "passive"))
    )
    (net (code "41") (name "Net-(POWER/GNDB-S)") (class "Default")
      (node (ref "F2") (pin "2") (pinfunction "2_2") (pintype "bidirectional"))
      (node (ref "POWER/GND") (pin "2") (pinfunction "S_2") (pintype "passive"))
    )
    (net (code "42") (name "Net-(PRECHARGE/AIRSA-S)") (class "Default")
      (node (ref "K2") (pin "2") (pinfunction "2_2") (pintype "bidirectional"))
      (node (ref "PRECHARGE/AIRS") (pin "1") (pinfunction "S_1") (pintype "passive"))
    )
    (net (code "43") (name "Net-(PRECHARGE/AIRSB-S)") (class "Default")
      (node (ref "K2") (pin "3") (pinfunction "3_3") (pintype "bidirectional"))
      (node (ref "PRECHARGE/AIRS") (pin "2") (pinfunction "S_2") (pintype "passive"))
    )
    (net (code "44") (name "OK_HS") (class "Default")
      (node (ref "ISOMETER_I/O") (pin "8") (pinfunction "8_8") (pintype "passive"))
      (node (ref "OK2") (pin "2") (pinfunction "A_2") (pintype "passive"))
      (node (ref "TP10") (pin "TP") (pinfunction "TP_TP") (pintype "input"))
    )
    (net (code "45") (name "PRECHARGE_EMSDC2") (class "Default")
      (node (ref "EMSDC") (pin "1") (pinfunction "S_1") (pintype "passive"))
      (node (ref "K6") (pin "3") (pinfunction "COM_3") (pintype "bidirectional"))
    )
    (net (code "46") (name "PRECHARGE_SELECT") (class "Default")
      (node (ref "BMS_I/O") (pin "7") (pinfunction "7_7") (pintype "passive"))
      (node (ref "D1") (pin "A") (pinfunction "A_A") (pintype "passive"))
      (node (ref "K2") (pin "5") (pinfunction "5_5") (pintype "bidirectional"))
      (node (ref "LED1") (pin "C") (pinfunction "C_C") (pintype "passive"))
      (node (ref "TP23") (pin "TP") (pinfunction "TP_TP") (pintype "input"))
    )
    (net (code "47") (name "READY_POWER") (class "Default")
      (node (ref "BMS_POWER/GND") (pin "1") (pinfunction "S_1") (pintype "passive"))
      (node (ref "D2") (pin "2") (pinfunction "A_2") (pintype "bidirectional"))
      (node (ref "F2") (pin "1") (pinfunction "1_1") (pintype "bidirectional"))
      (node (ref "THERMAL_EX_I/0") (pin "1") (pinfunction "1_1") (pintype "passive"))
      (node (ref "WIFI_MODULE") (pin "1") (pinfunction "1_1") (pintype "passive"))
    )
    (net (code "48") (name "STARTUP_RESET") (class "Default")
      (node (ref "IC1") (pin "3") (pinfunction "R0_3") (pintype "input"))
      (node (ref "IC1") (pin "7") (pinfunction "R1_7") (pintype "input"))
      (node (ref "IC2") (pin "3") (pinfunction "Q_3") (pintype "output"))
      (node (ref "R9") (pin "2") (pinfunction "2_2") (pintype "passive"))
      (node (ref "TP4") (pin "TP") (pinfunction "TP_TP") (pintype "input"))
    )
    (net (code "49") (name "unconnected-(BMS_I/O-Pad5)") (class "Default")
      (node (ref "BMS_I/O") (pin "5") (pinfunction "5_5") (pintype "passive"))
    )
    (net (code "50") (name "unconnected-(CAN1-Pad1)") (class "Default")
      (node (ref "CAN1") (pin "1") (pinfunction "1_1") (pintype "bidirectional"))
    )
    (net (code "51") (name "unconnected-(CAN1-Pad2)") (class "Default")
      (node (ref "CAN1") (pin "2") (pinfunction "2_2") (pintype "bidirectional"))
    )
    (net (code "52") (name "unconnected-(CAN1-Pad4)") (class "Default")
      (node (ref "CAN1") (pin "4") (pinfunction "4_4") (pintype "bidirectional"))
    )
    (net (code "53") (name "unconnected-(CAN1-Pad6)") (class "Default")
      (node (ref "CAN1") (pin "6") (pinfunction "6_6") (pintype "bidirectional"))
    )
    (net (code "54") (name "unconnected-(CAN1-Pad7)") (class "Default")
      (node (ref "CAN1") (pin "7") (pinfunction "7_7") (pintype "bidirectional"))
    )
    (net (code "55") (name "unconnected-(CAN1-Pad8)") (class "Default")
      (node (ref "CAN1") (pin "8") (pinfunction "8_8") (pintype "bidirectional"))
    )
    (net (code "56") (name "unconnected-(CAN1-Pad9)") (class "Default")
      (node (ref "CAN1") (pin "9") (pinfunction "9_9") (pintype "bidirectional"))
    )
    (net (code "57") (name "unconnected-(CAN1-PadMH1)") (class "Default")
      (node (ref "CAN1") (pin "MH1") (pinfunction "MH1_MH1") (pintype "bidirectional"))
    )
    (net (code "58") (name "unconnected-(CAN1-PadMH2)") (class "Default")
      (node (ref "CAN1") (pin "MH2") (pinfunction "MH2_MH2") (pintype "bidirectional"))
    )
    (net (code "59") (name "unconnected-(CAN2-Pad1)") (class "Default")
      (node (ref "CAN2") (pin "1") (pinfunction "1_1") (pintype "bidirectional"))
    )
    (net (code "60") (name "unconnected-(CAN2-Pad2)") (class "Default")
      (node (ref "CAN2") (pin "2") (pinfunction "2_2") (pintype "bidirectional"))
    )
    (net (code "61") (name "unconnected-(CAN2-Pad4)") (class "Default")
      (node (ref "CAN2") (pin "4") (pinfunction "4_4") (pintype "bidirectional"))
    )
    (net (code "62") (name "unconnected-(CAN2-Pad6)") (class "Default")
      (node (ref "CAN2") (pin "6") (pinfunction "6_6") (pintype "bidirectional"))
    )
    (net (code "63") (name "unconnected-(CAN2-Pad7)") (class "Default")
      (node (ref "CAN2") (pin "7") (pinfunction "7_7") (pintype "bidirectional"))
    )
    (net (code "64") (name "unconnected-(CAN2-Pad8)") (class "Default")
      (node (ref "CAN2") (pin "8") (pinfunction "8_8") (pintype "bidirectional"))
    )
    (net (code "65") (name "unconnected-(CAN2-Pad9)") (class "Default")
      (node (ref "CAN2") (pin "9") (pinfunction "9_9") (pintype "bidirectional"))
    )
    (net (code "66") (name "unconnected-(CAN2-PadMH1)") (class "Default")
      (node (ref "CAN2") (pin "MH1") (pinfunction "MH1_MH1") (pintype "bidirectional"))
    )
    (net (code "67") (name "unconnected-(CAN2-PadMH2)") (class "Default")
      (node (ref "CAN2") (pin "MH2") (pinfunction "MH2_MH2") (pintype "bidirectional"))
    )
    (net (code "68") (name "unconnected-(IC1A-Q2-Pad10)") (class "Default")
      (node (ref "IC1") (pin "10") (pinfunction "Q2_10") (pintype "output"))
    )
    (net (code "69") (name "unconnected-(IC1A-Q3-Pad1)") (class "Default")
      (node (ref "IC1") (pin "1") (pinfunction "Q3_1") (pintype "output"))
    )
    (net (code "70") (name "unconnected-(ISOMETER_I/O-Pad4)") (class "Default")
      (node (ref "ISOMETER_I/O") (pin "4") (pinfunction "4_4") (pintype "passive"))
    )
    (net (code "71") (name "unconnected-(ISOMETER_I/O-Pad6)") (class "Default")
      (node (ref "ISOMETER_I/O") (pin "6") (pinfunction "6_6") (pintype "passive"))
    )
    (net (code "72") (name "unconnected-(ISOMETER_I/O-Pad7)") (class "Default")
      (node (ref "ISOMETER_I/O") (pin "7") (pinfunction "7_7") (pintype "passive"))
    )
    (net (code "73") (name "unconnected-(THERMAL_EX_I/0-Pad7)") (class "Default")
      (node (ref "THERMAL_EX_I/0") (pin "7") (pinfunction "7_7") (pintype "passive"))
    )
    (net (code "74") (name "unconnected-(WIFI_MODULE-Pad4)") (class "Default")
      (node (ref "WIFI_MODULE") (pin "4") (pinfunction "4_4") (pintype "passive"))
    )
    (net (code "75") (name "unconnected-(WIFI_MODULE-Pad6)") (class "Default")
      (node (ref "WIFI_MODULE") (pin "6") (pinfunction "6_6") (pintype "passive"))
    )
    (net (code "76") (name "unconnected-(WIFI_MODULE-Pad7)") (class "Default")
      (node (ref "WIFI_MODULE") (pin "7") (pinfunction "7_7") (pintype "passive"))
    )
  )
)
